# creekboard.net
KiCad netlist of a schematic drawn in EAGLE
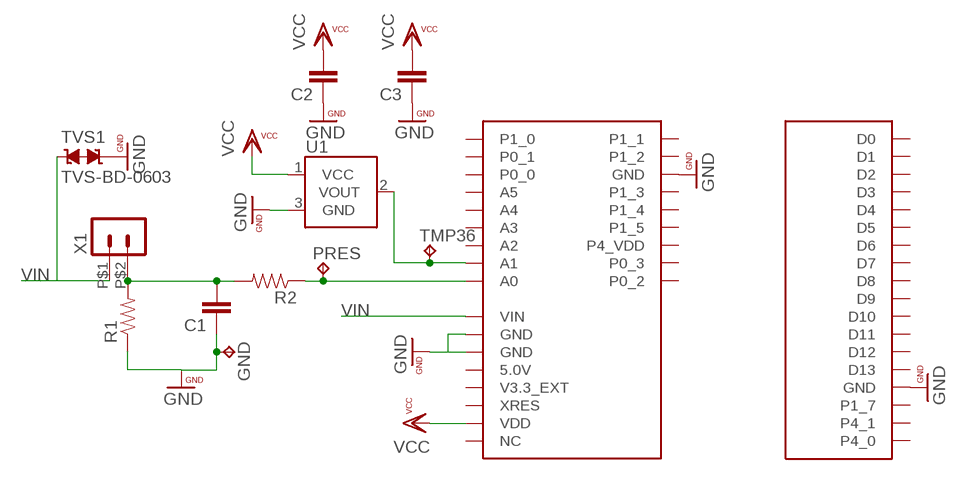
[diagram p0: schematic, sheet 1]

(export (version "E")
  (design (tool "Eeschema 10.0.6"))
  (components
    (comp (ref "C1")
      (value "CAP0603-CAP")
      (footprint "eagle-import:0603-CAP")
      (libsource (lib "eagle-import") (part "CAP0603-CAP"))
    )
    (comp (ref "C2")
      (value "CAP0603-CAP")
      (footprint "eagle-import:0603-CAP")
      (libsource (lib "eagle-import") (part "CAP0603-CAP"))
    )
    (comp (ref "C3")
      (value "CAP0603-CAP")
      (footprint "eagle-import:0603-CAP")
      (libsource (lib "eagle-import") (part "CAP0603-CAP"))
    )
    (comp (ref "GND")
      (value "TP-040")
      (footprint "eagle-import:TP-040")
      (libsource (lib "eagle-import") (part "TP-040"))
    )
    (comp (ref "PRES")
      (value "TP-040")
      (footprint "eagle-import:TP-040")
      (libsource (lib "eagle-import") (part "TP-040"))
    )
    (comp (ref "R1")
      (value "RESISTOR0805-RES")
      (footprint "eagle-import:0805")
      (libsource (lib "eagle-import") (part "RESISTOR0805-RES"))
    )
    (comp (ref "R2")
      (value "RESISTOR0603-RES")
      (footprint "eagle-import:0603-RES")
      (libsource (lib "eagle-import") (part "RESISTOR0603-RES"))
    )
    (comp (ref "TMP36")
      (value "TP-040")
      (footprint "eagle-import:TP-040")
      (libsource (lib "eagle-import") (part "TP-040"))
    )
    (comp (ref "TVS1")
      (value "TVS-BD-0603")
      (footprint "eagle-import:TVS0603")
      (libsource (lib "eagle-import") (part "TVS-BD-0603"))
    )
    (comp (ref "U1")
      (value "TMP36GT9")
      (footprint "eagle-import:TO-92")
      (libsource (lib "eagle-import") (part "TMP36GT9"))
    )
    (comp (ref "U2")
      (value "PIONEERNO_SILK")
      (footprint "eagle-import:PIONEER")
      (libsource (lib "eagle-import") (part "PIONEERNO_SILK"))
    )
    (comp (ref "X1")
      (value "HEADER_POS2_43650-0200")
      (footprint "eagle-import:43650-0200")
      (libsource (lib "eagle-import") (part "HEADER_POS2_?43650-0200"))
    )
  )
  (nets
    (net (code "1") (name "/VIN") (class "Default")
      (node (ref "TVS1") (pin "1") (pinfunction "1_1") (pintype "passive"))
      (node (ref "U2") (pin "VIN") (pinfunction "VIN_VIN") (pintype "bidirectional"))
      (node (ref "X1") (pin "P$1") (pinfunction "1_P$1") (pintype "passive"))
    )
    (net (code "2") (name "GND") (class "Default")
      (node (ref "C1") (pin "1") (pinfunction "1_1") (pintype "passive"))
      (node (ref "C2") (pin "1") (pinfunction "1_1") (pintype "passive"))
      (node (ref "C3") (pin "1") (pinfunction "1_1") (pintype "passive"))
      (node (ref "GND") (pin "1") (pinfunction "1_1") (pintype "passive"))
      (node (ref "R1") (pin "1") (pinfunction "1_1") (pintype "passive"))
      (node (ref "TVS1") (pin "2") (pinfunction "2_2") (pintype "passive"))
      (node (ref "U1") (pin "3") (pinfunction "GND_3") (pintype "bidirectional"))
      (node (ref "U2") (pin "GND@2") (pinfunction "GND_GND@2") (pintype "bidirectional"))
      (node (ref "U2") (pin "GND@3") (pinfunction "GND_GND@3") (pintype "bidirectional"))
      (node (ref "U2") (pin "GND@3R") (pinfunction "GND_GND@3R") (pintype "bidirectional"))
      (node (ref "U2") (pin "GND@7") (pinfunction "GND_GND@7") (pintype "bidirectional"))
    )
    (net (code "3") (name "Net-(PRES-Pad1)") (class "Default")
      (node (ref "PRES") (pin "1") (pinfunction "1_1") (pintype "passive"))
      (node (ref "R2") (pin "1") (pinfunction "1_1") (pintype "passive"))
      (node (ref "U2") (pin "A0") (pinfunction "A0_A0") (pintype "bidirectional"))
    )
    (net (code "4") (name "Net-(U1-VOUT)") (class "Default")
      (node (ref "TMP36") (pin "1") (pinfunction "1_1") (pintype "passive"))
      (node (ref "U1") (pin "2") (pinfunction "VOUT_2") (pintype "bidirectional"))
      (node (ref "U2") (pin "A1") (pinfunction "A1_A1") (pintype "bidirectional"))
    )
    (net (code "5") (name "Net-(X1-2)") (class "Default")
      (node (ref "C1") (pin "2") (pinfunction "2_2") (pintype "passive"))
      (node (ref "R1") (pin "2") (pinfunction "2_2") (pintype "passive"))
      (node (ref "R2") (pin "2") (pinfunction "2_2") (pintype "passive"))
      (node (ref "X1") (pin "P$2") (pinfunction "2_P$2") (pintype "passive"))
    )
    (net (code "6") (name "VCC") (class "Default")
      (node (ref "C2") (pin "2") (pinfunction "2_2") (pintype "passive"))
      (node (ref "C3") (pin "2") (pinfunction "2_2") (pintype "passive"))
      (node (ref "U1") (pin "1") (pinfunction "VCC_1") (pintype "bidirectional"))
      (node (ref "U2") (pin "P4_VDD1") (pinfunction "VDD_P4_VDD1") (pintype "bidirectional"))
    )
    (net (code "7") (name "unconnected-(U2-5.0V-Pad5V)") (class "Default")
      (node (ref "U2") (pin "5V") (pinfunction "5.0V_5V") (pintype "bidirectional"))
    )
    (net (code "8") (name "unconnected-(U2-NC-PadNC@8)") (class "Default")
      (node (ref "U2") (pin "NC@8") (pinfunction "NC_NC@8") (pintype "bidirectional"))
    )
    (net (code "9") (name "unconnected-(U2-P1_7-PadAREF)") (class "Default")
      (node (ref "U2") (pin "AREF") (pinfunction "P1_7_AREF") (pintype "bidirectional"))
    )
    (net (code "10") (name "unconnected-(U2-P4_0-PadSCL)") (class "Default")
      (node (ref "U2") (pin "SCL") (pinfunction "P4_0_SCL") (pintype "bidirectional"))
    )
    (net (code "11") (name "unconnected-(U2-P4_1-PadSDA)") (class "Default")
      (node (ref "U2") (pin "SDA") (pinfunction "P4_1_SDA") (pintype "bidirectional"))
    )
    (net (code "12") (name "unconnected-(U2-PadA2)") (class "Default")
      (node (ref "U2") (pin "A2") (pinfunction "A2_A2") (pintype "bidirectional"))
    )
    (net (code "13") (name "unconnected-(U2-PadA3)") (class "Default")
      (node (ref "U2") (pin "A3") (pinfunction "A3_A3") (pintype "bidirectional"))
    )
    (net (code "14") (name "unconnected-(U2-PadA4)") (class "Default")
      (node (ref "U2") (pin "A4") (pinfunction "A4_A4") (pintype "bidirectional"))
    )
    (net (code "15") (name "unconnected-(U2-PadA5)") (class "Default")
      (node (ref "U2") (pin "A5") (pinfunction "A5_A5") (pintype "bidirectional"))
    )
    (net (code "16") (name "unconnected-(U2-PadD0)") (class "Default")
      (node (ref "U2") (pin "D0") (pinfunction "D0_D0") (pintype "bidirectional"))
    )
    (net (code "17") (name "unconnected-(U2-PadD1)") (class "Default")
      (node (ref "U2") (pin "D1") (pinfunction "D1_D1") (pintype "bidirectional"))
    )
    (net (code "18") (name "unconnected-(U2-PadD2)") (class "Default")
      (node (ref "U2") (pin "D2") (pinfunction "D2_D2") (pintype "bidirectional"))
    )
    (net (code "19") (name "unconnected-(U2-PadD3)") (class "Default")
      (node (ref "U2") (pin "D3") (pinfunction "D3_D3") (pintype "bidirectional"))
    )
    (net (code "20") (name "unconnected-(U2-PadD4)") (class "Default")
      (node (ref "U2") (pin "D4") (pinfunction "D4_D4") (pintype "bidirectional"))
    )
    (net (code "21") (name "unconnected-(U2-PadD5)") (class "Default")
      (node (ref "U2") (pin "D5") (pinfunction "D5_D5") (pintype "bidirectional"))
    )
    (net (code "22") (name "unconnected-(U2-PadD6)") (class "Default")
      (node (ref "U2") (pin "D6") (pinfunction "D6_D6") (pintype "bidirectional"))
    )
    (net (code "23") (name "unconnected-(U2-PadD7)") (class "Default")
      (node (ref "U2") (pin "D7") (pinfunction "D7_D7") (pintype "bidirectional"))
    )
    (net (code "24") (name "unconnected-(U2-PadD8)") (class "Default")
      (node (ref "U2") (pin "D8") (pinfunction "D8_D8") (pintype "bidirectional"))
    )
    (net (code "25") (name "unconnected-(U2-PadD9)") (class "Default")
      (node (ref "U2") (pin "D9") (pinfunction "D9_D9") (pintype "bidirectional"))
    )
    (net (code "26") (name "unconnected-(U2-PadD10)") (class "Default")
      (node (ref "U2") (pin "D10") (pinfunction "D10_D10") (pintype "bidirectional"))
    )
    (net (code "27") (name "unconnected-(U2-PadD11)") (class "Default")
      (node (ref "U2") (pin "D11") (pinfunction "D11_D11") (pintype "bidirectional"))
    )
    (net (code "28") (name "unconnected-(U2-PadD12)") (class "Default")
      (node (ref "U2") (pin "D12") (pinfunction "D12_D12") (pintype "bidirectional"))
    )
    (net (code "29") (name "unconnected-(U2-PadD13)") (class "Default")
      (node (ref "U2") (pin "D13") (pinfunction "D13_D13") (pintype "bidirectional"))
    )
    (net (code "30") (name "unconnected-(U2-PadP0_0)") (class "Default")
      (node (ref "U2") (pin "P0_0") (pinfunction "P0_0_P0_0") (pintype "bidirectional"))
    )
    (net (code "31") (name "unconnected-(U2-PadP0_1)") (class "Default")
      (node (ref "U2") (pin "P0_1") (pinfunction "P0_1_P0_1") (pintype "bidirectional"))
    )
    (net (code "32") (name "unconnected-(U2-PadP0_2)") (class "Default")
      (node (ref "U2") (pin "P0_2") (pinfunction "P0_2_P0_2") (pintype "bidirectional"))
    )
    (net (code "33") (name "unconnected-(U2-PadP0_3)") (class "Default")
      (node (ref "U2") (pin "P0_3") (pinfunction "P0_3_P0_3") (pintype "bidirectional"))
    )
    (net (code "34") (name "unconnected-(U2-PadP1_0)") (class "Default")
      (node (ref "U2") (pin "P1_0") (pinfunction "P1_0_P1_0") (pintype "bidirectional"))
    )
    (net (code "35") (name "unconnected-(U2-PadP1_1)") (class "Default")
      (node (ref "U2") (pin "P1_1") (pinfunction "P1_1_P1_1") (pintype "bidirectional"))
    )
    (net (code "36") (name "unconnected-(U2-PadP1_2)") (class "Default")
      (node (ref "U2") (pin "P1_2") (pinfunction "P1_2_P1_2") (pintype "bidirectional"))
    )
    (net (code "37") (name "unconnected-(U2-PadP1_3)") (class "Default")
      (node (ref "U2") (pin "P1_3") (pinfunction "P1_3_P1_3") (pintype "bidirectional"))
    )
    (net (code "38") (name "unconnected-(U2-PadP1_4)") (class "Default")
      (node (ref "U2") (pin "P1_4") (pinfunction "P1_4_P1_4") (pintype "bidirectional"))
    )
    (net (code "39") (name "unconnected-(U2-PadP1_5)") (class "Default")
      (node (ref "U2") (pin "P1_5") (pinfunction "P1_5_P1_5") (pintype "bidirectional"))
    )
    (net (code "40") (name "unconnected-(U2-PadP4_VDD)") (class "Default")
      (node (ref "U2") (pin "P4_VDD") (pinfunction "P4_VDD_P4_VDD") (pintype "bidirectional"))
    )
    (net (code "41") (name "unconnected-(U2-PadXRES)") (class "Default")
      (node (ref "U2") (pin "XRES") (pinfunction "XRES_XRES") (pintype "bidirectional"))
    )
    (net (code "42") (name "unconnected-(U2-V3.3_EXT-Pad3.3V)") (class "Default")
      (node (ref "U2") (pin "3.3V") (pinfunction "V3.3_EXT_3.3V") (pintype "bidirectional"))
    )
  )
)
